# SigFoxBatteryMonitor.net
KiCad netlist of a schematic drawn in EAGLE
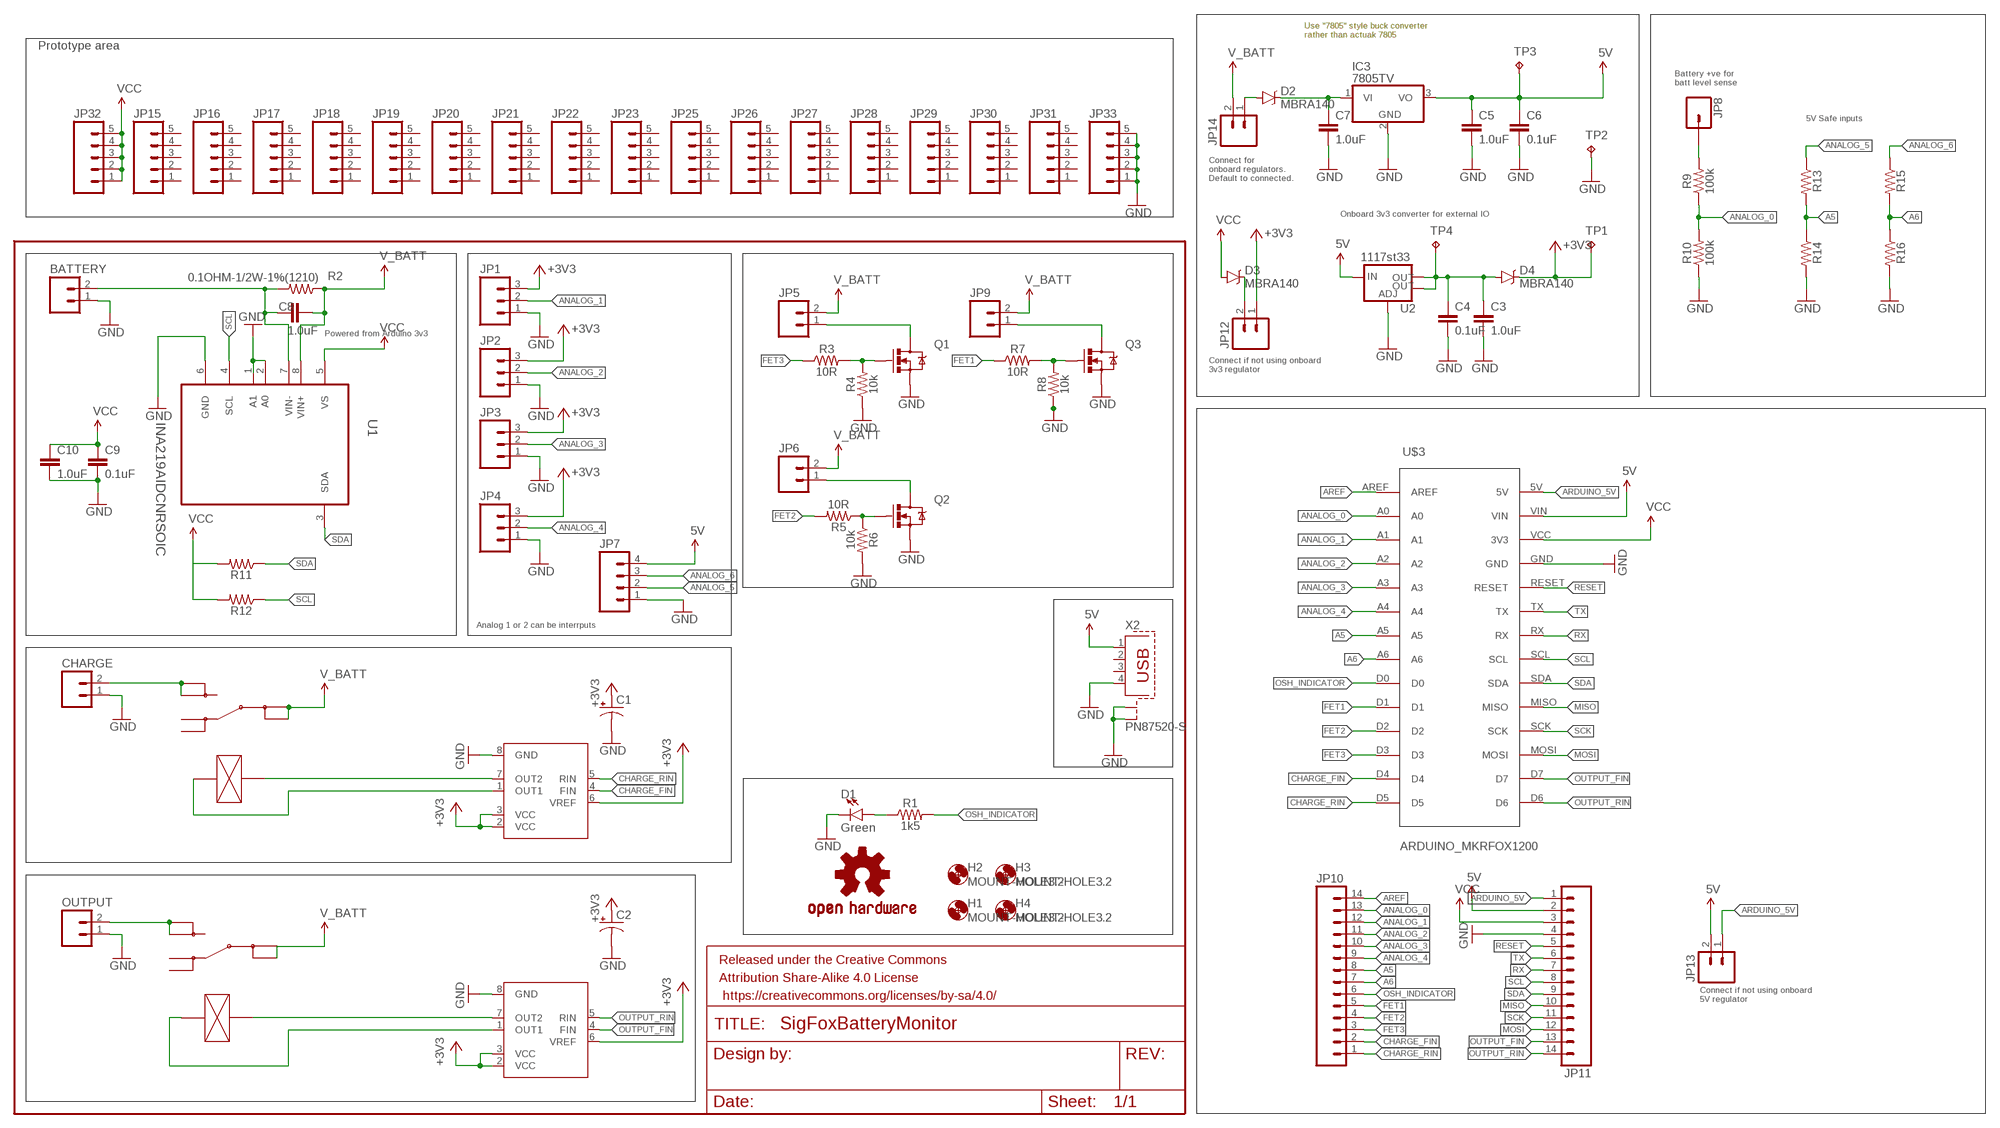
[diagram p0: schematic, sheet 1]

(export (version "E")
  (design (tool "Eeschema 10.0.6"))
  (components
    (comp (ref "BATTERY")
      (value "M025MM")
      (footprint "eagle-import:SCREWTERMINAL-5MM-2")
      (libsource (lib "eagle-import") (part "M025MM"))
    )
    (comp (ref "C1")
      (value "CAP_POL1206")
      (footprint "eagle-import:EIA3216")
      (libsource (lib "eagle-import") (part "CAP_POL1206"))
    )
    (comp (ref "C2")
      (value "CAP_POL1206")
      (footprint "eagle-import:EIA3216")
      (libsource (lib "eagle-import") (part "CAP_POL1206"))
    )
    (comp (ref "C3")
      (value "1.0uF")
      (footprint "eagle-import:0805")
      (libsource (lib "eagle-import") (part "1.0UF-0805-25V-10%"))
    )
    (comp (ref "C4")
      (value "0.1uF")
      (footprint "eagle-import:0805")
      (libsource (lib "eagle-import") (part "1.0UF-0805-25V-10%"))
    )
    (comp (ref "C5")
      (value "1.0uF")
      (footprint "eagle-import:0805")
      (libsource (lib "eagle-import") (part "1.0UF-0805-25V-10%"))
    )
    (comp (ref "C6")
      (value "0.1uF")
      (footprint "eagle-import:0805")
      (libsource (lib "eagle-import") (part "1.0UF-0805-25V-10%"))
    )
    (comp (ref "C7")
      (value "1.0uF")
      (footprint "eagle-import:0805")
      (libsource (lib "eagle-import") (part "1.0UF-0805-25V-10%"))
    )
    (comp (ref "C8")
      (value "1.0uF")
      (footprint "eagle-import:0805")
      (libsource (lib "eagle-import") (part "1.0UF-0805-25V-10%"))
    )
    (comp (ref "C9")
      (value "0.1uF")
      (footprint "eagle-import:0805")
      (libsource (lib "eagle-import") (part "1.0UF-0805-25V-10%"))
    )
    (comp (ref "C10")
      (value "1.0uF")
      (footprint "eagle-import:0805")
      (libsource (lib "eagle-import") (part "1.0UF-0805-25V-10%"))
    )
    (comp (ref "CHARGE")
      (value "M025MM")
      (footprint "eagle-import:SCREWTERMINAL-5MM-2")
      (libsource (lib "eagle-import") (part "M025MM"))
    )
    (comp (ref "D1")
      (value "Green")
      (footprint "eagle-import:LED-1206-BOTTOM")
      (libsource (lib "eagle-import") (part "LED-GREEN1206-BOTTOM"))
    )
    (comp (ref "D2")
      (value "MBRA140")
      (footprint "eagle-import:SMA-DIODE")
      (libsource (lib "eagle-import") (part "DIODE-SCHOTTKY-MBRA140"))
    )
    (comp (ref "D3")
      (value "MBRA140")
      (footprint "eagle-import:SMA-DIODE")
      (libsource (lib "eagle-import") (part "DIODE-SCHOTTKY-MBRA140"))
    )
    (comp (ref "D4")
      (value "MBRA140")
      (footprint "eagle-import:SMA-DIODE")
      (libsource (lib "eagle-import") (part "DIODE-SCHOTTKY-MBRA140"))
    )
    (comp (ref "FRAME1")
      (value "FRAME-LETTER")
      (footprint "eagle-import:CREATIVE_COMMONS")
      (libsource (lib "eagle-import") (part "FRAME-LETTER"))
    )
    (comp (ref "H1")
      (value "MOUNT-HOLE3.2")
      (footprint "eagle-import:3,2")
      (libsource (lib "eagle-import") (part "MOUNT-HOLE3.2"))
    )
    (comp (ref "H2")
      (value "MOUNT-HOLE3.2")
      (footprint "eagle-import:3,2")
      (libsource (lib "eagle-import") (part "MOUNT-HOLE3.2"))
    )
    (comp (ref "H3")
      (value "MOUNT-HOLE3.2")
      (footprint "eagle-import:3,2")
      (libsource (lib "eagle-import") (part "MOUNT-HOLE3.2"))
    )
    (comp (ref "H4")
      (value "MOUNT-HOLE3.2")
      (footprint "eagle-import:3,2")
      (libsource (lib "eagle-import") (part "MOUNT-HOLE3.2"))
    )
    (comp (ref "IC1")
      (value "BD6211F")
      (footprint "eagle-import:SOP8")
      (libsource (lib "eagle-import") (part "BD6211F"))
    )
    (comp (ref "IC2")
      (value "BD6211F")
      (footprint "eagle-import:SOP8")
      (libsource (lib "eagle-import") (part "BD6211F"))
    )
    (comp (ref "IC3")
      (value "7805TV")
      (footprint "eagle-import:TO220V")
      (libsource (lib "eagle-import") (part "78TV05"))
    )
    (comp (ref "JP1")
      (value "M03POLAR")
      (footprint "eagle-import:MOLEX-1X3")
      (libsource (lib "eagle-import") (part "M03POLAR"))
    )
    (comp (ref "JP2")
      (value "M03POLAR")
      (footprint "eagle-import:MOLEX-1X3")
      (libsource (lib "eagle-import") (part "M03POLAR"))
    )
    (comp (ref "JP3")
      (value "M03POLAR")
      (footprint "eagle-import:MOLEX-1X3")
      (libsource (lib "eagle-import") (part "M03POLAR"))
    )
    (comp (ref "JP4")
      (value "M03POLAR")
      (footprint "eagle-import:MOLEX-1X3")
      (libsource (lib "eagle-import") (part "M03POLAR"))
    )
    (comp (ref "JP5")
      (value "M02POLAR")
      (footprint "eagle-import:MOLEX-1X2")
      (libsource (lib "eagle-import") (part "M02POLAR"))
    )
    (comp (ref "JP6")
      (value "M02POLAR")
      (footprint "eagle-import:MOLEX-1X2")
      (libsource (lib "eagle-import") (part "M02POLAR"))
    )
    (comp (ref "JP7")
      (value "M04POLAR")
      (footprint "eagle-import:MOLEX-1X4")
      (libsource (lib "eagle-import") (part "M04POLAR"))
    )
    (comp (ref "JP8")
      (value "M01PTH")
      (footprint "eagle-import:1X01")
      (libsource (lib "eagle-import") (part "M01PTH"))
    )
    (comp (ref "JP9")
      (value "M02POLAR")
      (footprint "eagle-import:MOLEX-1X2")
      (libsource (lib "eagle-import") (part "M02POLAR"))
    )
    (comp (ref "JP10")
      (value "M14")
      (footprint "eagle-import:1X14")
      (libsource (lib "eagle-import") (part "M14"))
    )
    (comp (ref "JP11")
      (value "M14")
      (footprint "eagle-import:1X14")
      (libsource (lib "eagle-import") (part "M14"))
    )
    (comp (ref "JP12")
      (value "M02PTH")
      (footprint "eagle-import:1X02")
      (libsource (lib "eagle-import") (part "M02PTH"))
    )
    (comp (ref "JP13")
      (value "M02PTH")
      (footprint "eagle-import:1X02")
      (libsource (lib "eagle-import") (part "M02PTH"))
    )
    (comp (ref "JP14")
      (value "M02PTH")
      (footprint "eagle-import:1X02")
      (libsource (lib "eagle-import") (part "M02PTH"))
    )
    (comp (ref "JP15")
      (value "M05NO_SILK")
      (footprint "eagle-import:1X05_NO_SILK")
      (libsource (lib "eagle-import") (part "M05NO_SILK"))
    )
    (comp (ref "JP16")
      (value "M05NO_SILK")
      (footprint "eagle-import:1X05_NO_SILK")
      (libsource (lib "eagle-import") (part "M05NO_SILK"))
    )
    (comp (ref "JP17")
      (value "M05NO_SILK")
      (footprint "eagle-import:1X05_NO_SILK")
      (libsource (lib "eagle-import") (part "M05NO_SILK"))
    )
    (comp (ref "JP18")
      (value "M05NO_SILK")
      (footprint "eagle-import:1X05_NO_SILK")
      (libsource (lib "eagle-import") (part "M05NO_SILK"))
    )
    (comp (ref "JP19")
      (value "M05NO_SILK")
      (footprint "eagle-import:1X05_NO_SILK")
      (libsource (lib "eagle-import") (part "M05NO_SILK"))
    )
    (comp (ref "JP20")
      (value "M05NO_SILK")
      (footprint "eagle-import:1X05_NO_SILK")
      (libsource (lib "eagle-import") (part "M05NO_SILK"))
    )
    (comp (ref "JP21")
      (value "M05NO_SILK")
      (footprint "eagle-import:1X05_NO_SILK")
      (libsource (lib "eagle-import") (part "M05NO_SILK"))
    )
    (comp (ref "JP22")
      (value "M05NO_SILK")
      (footprint "eagle-import:1X05_NO_SILK")
      (libsource (lib "eagle-import") (part "M05NO_SILK"))
    )
    (comp (ref "JP23")
      (value "M05NO_SILK")
      (footprint "eagle-import:1X05_NO_SILK")
      (libsource (lib "eagle-import") (part "M05NO_SILK"))
    )
    (comp (ref "JP25")
      (value "M05NO_SILK")
      (footprint "eagle-import:1X05_NO_SILK")
      (libsource (lib "eagle-import") (part "M05NO_SILK"))
    )
    (comp (ref "JP26")
      (value "M05NO_SILK")
      (footprint "eagle-import:1X05_NO_SILK")
      (libsource (lib "eagle-import") (part "M05NO_SILK"))
    )
    (comp (ref "JP27")
      (value "M05NO_SILK")
      (footprint "eagle-import:1X05_NO_SILK")
      (libsource (lib "eagle-import") (part "M05NO_SILK"))
    )
    (comp (ref "JP28")
      (value "M05NO_SILK")
      (footprint "eagle-import:1X05_NO_SILK")
      (libsource (lib "eagle-import") (part "M05NO_SILK"))
    )
    (comp (ref "JP29")
      (value "M05NO_SILK")
      (footprint "eagle-import:1X05_NO_SILK")
      (libsource (lib "eagle-import") (part "M05NO_SILK"))
    )
    (comp (ref "JP30")
      (value "M05NO_SILK")
      (footprint "eagle-import:1X05_NO_SILK")
      (libsource (lib "eagle-import") (part "M05NO_SILK"))
    )
    (comp (ref "JP31")
      (value "M05NO_SILK")
      (footprint "eagle-import:1X05_NO_SILK")
      (libsource (lib "eagle-import") (part "M05NO_SILK"))
    )
    (comp (ref "JP32")
      (value "M05PTH")
      (footprint "eagle-import:1X05")
      (libsource (lib "eagle-import") (part "M05PTH"))
    )
    (comp (ref "JP33")
      (value "M05PTH")
      (footprint "eagle-import:1X05")
      (libsource (lib "eagle-import") (part "M05PTH"))
    )
    (comp (ref "LOGO1")
      (value "OSHW-LOGOM")
      (footprint "eagle-import:OSHW-LOGO-M")
      (libsource (lib "eagle-import") (part "OSHW-LOGOM"))
    )
    (comp (ref "OUTPUT")
      (value "M025MM")
      (footprint "eagle-import:SCREWTERMINAL-5MM-2")
      (libsource (lib "eagle-import") (part "M025MM"))
    )
    (comp (ref "Q1")
      (value "IRF7413Z")
      (footprint "eagle-import:SO08")
      (libsource (lib "eagle-import") (part "MOSFET-NCHANNELFDS6630A"))
    )
    (comp (ref "Q2")
      (value "IRF7413Z")
      (footprint "eagle-import:SO08")
      (libsource (lib "eagle-import") (part "MOSFET-NCHANNELFDS6630A"))
    )
    (comp (ref "Q3")
      (value "IRF7413Z")
      (footprint "eagle-import:SO08")
      (libsource (lib "eagle-import") (part "MOSFET-NCHANNELFDS6630A"))
    )
    (comp (ref "R1")
      (value "1k5")
      (footprint "eagle-import:1206")
      (libsource (lib "eagle-import") (part "RESISTOR1206"))
    )
    (comp (ref "R2")
      (value "0.1OHM-1/2W-1%(1210)")
      (footprint "eagle-import:1210")
      (libsource (lib "eagle-import") (part "0.1OHM-1/2W-1%(1210)"))
    )
    (comp (ref "R3")
      (value "10R")
      (footprint "eagle-import:0805")
      (libsource (lib "eagle-import") (part "RESISTOR0805"))
    )
    (comp (ref "R4")
      (value "10k")
      (footprint "eagle-import:0805")
      (libsource (lib "eagle-import") (part "RESISTOR0805"))
    )
    (comp (ref "R5")
      (value "10R")
      (footprint "eagle-import:0805")
      (libsource (lib "eagle-import") (part "RESISTOR0805"))
    )
    (comp (ref "R6")
      (value "10k")
      (footprint "eagle-import:0805")
      (libsource (lib "eagle-import") (part "RESISTOR0805"))
    )
    (comp (ref "R7")
      (value "10R")
      (footprint "eagle-import:0805")
      (libsource (lib "eagle-import") (part "RESISTOR0805"))
    )
    (comp (ref "R8")
      (value "10k")
      (footprint "eagle-import:0805")
      (libsource (lib "eagle-import") (part "RESISTOR0805"))
    )
    (comp (ref "R9")
      (value "100k")
      (footprint "eagle-import:0805")
      (libsource (lib "eagle-import") (part "RESISTOR0805"))
    )
    (comp (ref "R10")
      (value "100k")
      (footprint "eagle-import:0805")
      (libsource (lib "eagle-import") (part "RESISTOR0805"))
    )
    (comp (ref "R11")
      (value "RESISTOR0805")
      (footprint "eagle-import:0805")
      (libsource (lib "eagle-import") (part "RESISTOR0805"))
    )
    (comp (ref "R12")
      (value "RESISTOR0805")
      (footprint "eagle-import:0805")
      (libsource (lib "eagle-import") (part "RESISTOR0805"))
    )
    (comp (ref "R13")
      (value "RESISTOR0805")
      (footprint "eagle-import:0805")
      (libsource (lib "eagle-import") (part "RESISTOR0805"))
    )
    (comp (ref "R14")
      (value "RESISTOR0805")
      (footprint "eagle-import:0805")
      (libsource (lib "eagle-import") (part "RESISTOR0805"))
    )
    (comp (ref "R15")
      (value "RESISTOR0805")
      (footprint "eagle-import:0805")
      (libsource (lib "eagle-import") (part "RESISTOR0805"))
    )
    (comp (ref "R16")
      (value "RESISTOR0805")
      (footprint "eagle-import:0805")
      (libsource (lib "eagle-import") (part "RESISTOR0805"))
    )
    (comp (ref "TP1")
      (value "3v3")
      (footprint "eagle-import:TP15R")
      (libsource (lib "eagle-import") (part "TPTP15R"))
    )
    (comp (ref "TP2")
      (value "GND")
      (footprint "eagle-import:TP15R")
      (libsource (lib "eagle-import") (part "TPTP15R"))
    )
    (comp (ref "TP3")
      (value "5v")
      (footprint "eagle-import:TP15R")
      (libsource (lib "eagle-import") (part "TPTP15R"))
    )
    (comp (ref "TP4")
      (value "5v")
      (footprint "eagle-import:TP15R")
      (libsource (lib "eagle-import") (part "TPTP15R"))
    )
    (comp (ref "U$1")
      (value "RELAY_G5RL-1E")
      (footprint "eagle-import:G5RL-1E")
      (libsource (lib "eagle-import") (part "RELAY_G5RL-1E"))
    )
    (comp (ref "U$2")
      (value "RELAY_G5RL-1E")
      (footprint "eagle-import:G5RL-1E")
      (libsource (lib "eagle-import") (part "RELAY_G5RL-1E"))
    )
    (comp (ref "U$3")
      (value "ARDUINO_MKRFOX1200")
      (footprint "eagle-import:ARDUINO_MKRFOX1200")
      (libsource (lib "eagle-import") (part "ARDUINO_MKRFOX1200"))
    )
    (comp (ref "U1")
      (value "INA219AIDCNRSOIC")
      (footprint "eagle-import:SO08")
      (libsource (lib "eagle-import") (part "INA219AIDCNRSOIC"))
    )
    (comp (ref "U2")
      (value "1117st33")
      (footprint "eagle-import:SOT223")
      (libsource (lib "eagle-import") (part "V_REG_LM1117SOT223"))
    )
    (comp (ref "X2")
      (value "PN87520-S")
      (footprint "eagle-import:PN87520-S")
      (libsource (lib "eagle-import") (part "PN87520-S"))
    )
  )
  (nets
    (net (code "1") (name "+3V3") (class "Default")
      (node (ref "C1") (pin "A") (pinfunction "+_A") (pintype "passive"))
      (node (ref "C2") (pin "A") (pinfunction "+_A") (pintype "passive"))
      (node (ref "D4") (pin "C") (pinfunction "C_C") (pintype "passive"))
      (node (ref "IC1") (pin "2") (pinfunction "VCC_2") (pintype "power_in"))
      (node (ref "IC1") (pin "3") (pinfunction "VCC_3") (pintype "power_in"))
      (node (ref "IC1") (pin "6") (pinfunction "VREF_6") (pintype "passive"))
      (node (ref "IC2") (pin "2") (pinfunction "VCC_2") (pintype "power_in"))
      (node (ref "IC2") (pin "3") (pinfunction "VCC_3") (pintype "power_in"))
      (node (ref "IC2") (pin "6") (pinfunction "VREF_6") (pintype "passive"))
      (node (ref "JP1") (pin "3") (pinfunction "3_3") (pintype "passive"))
      (node (ref "JP12") (pin "1") (pinfunction "1_1") (pintype "passive"))
      (node (ref "JP2") (pin "3") (pinfunction "3_3") (pintype "passive"))
      (node (ref "JP3") (pin "3") (pinfunction "3_3") (pintype "passive"))
      (node (ref "JP4") (pin "3") (pinfunction "3_3") (pintype "passive"))
      (node (ref "TP1") (pin "TP") (pinfunction "TP_TP") (pintype "input"))
    )
    (net (code "2") (name "5V") (class "Default")
      (node (ref "C5") (pin "1") (pinfunction "1_1") (pintype "passive"))
      (node (ref "C6") (pin "1") (pinfunction "1_1") (pintype "passive"))
      (node (ref "IC3") (pin "3") (pinfunction "VO_3") (pintype "passive"))
      (node (ref "JP11") (pin "2") (pinfunction "2_2") (pintype "passive"))
      (node (ref "JP13") (pin "2") (pinfunction "2_2") (pintype "passive"))
      (node (ref "JP7") (pin "4") (pinfunction "4_4") (pintype "passive"))
      (node (ref "TP3") (pin "TP") (pinfunction "TP_TP") (pintype "input"))
      (node (ref "U$3") (pin "VIN") (pinfunction "VIN_VIN") (pintype "input"))
      (node (ref "U2") (pin "3") (pinfunction "IN_3") (pintype "input"))
      (node (ref "X2") (pin "1") (pinfunction "1_1") (pintype "passive"))
    )
    (net (code "3") (name "A5") (class "Default")
      (node (ref "JP10") (pin "8") (pinfunction "8_8") (pintype "passive"))
      (node (ref "R13") (pin "2") (pinfunction "2_2") (pintype "passive"))
      (node (ref "R14") (pin "1") (pinfunction "1_1") (pintype "passive"))
      (node (ref "U$3") (pin "A5") (pinfunction "A5_A5") (pintype "bidirectional"))
    )
    (net (code "4") (name "A6") (class "Default")
      (node (ref "JP10") (pin "7") (pinfunction "7_7") (pintype "passive"))
      (node (ref "R15") (pin "2") (pinfunction "2_2") (pintype "passive"))
      (node (ref "R16") (pin "1") (pinfunction "1_1") (pintype "passive"))
      (node (ref "U$3") (pin "A6") (pinfunction "A6_A6") (pintype "bidirectional"))
    )
    (net (code "5") (name "ANALOG_0") (class "Default")
      (node (ref "JP10") (pin "13") (pinfunction "13_13") (pintype "passive"))
      (node (ref "R10") (pin "2") (pinfunction "2_2") (pintype "passive"))
      (node (ref "R9") (pin "1") (pinfunction "1_1") (pintype "passive"))
      (node (ref "U$3") (pin "A0") (pinfunction "A0_A0") (pintype "bidirectional"))
    )
    (net (code "6") (name "ANALOG_1") (class "Default")
      (node (ref "JP1") (pin "2") (pinfunction "2_2") (pintype "passive"))
      (node (ref "JP10") (pin "12") (pinfunction "12_12") (pintype "passive"))
      (node (ref "U$3") (pin "A1") (pinfunction "A1_A1") (pintype "bidirectional"))
    )
    (net (code "7") (name "ANALOG_2") (class "Default")
      (node (ref "JP10") (pin "11") (pinfunction "11_11") (pintype "passive"))
      (node (ref "JP2") (pin "2") (pinfunction "2_2") (pintype "passive"))
      (node (ref "U$3") (pin "A2") (pinfunction "A2_A2") (pintype "bidirectional"))
    )
    (net (code "8") (name "ANALOG_3") (class "Default")
      (node (ref "JP10") (pin "10") (pinfunction "10_10") (pintype "passive"))
      (node (ref "JP3") (pin "2") (pinfunction "2_2") (pintype "passive"))
      (node (ref "U$3") (pin "A3") (pinfunction "A3_A3") (pintype "bidirectional"))
    )
    (net (code "9") (name "ANALOG_4") (class "Default")
      (node (ref "JP10") (pin "9") (pinfunction "9_9") (pintype "passive"))
      (node (ref "JP4") (pin "2") (pinfunction "2_2") (pintype "passive"))
      (node (ref "U$3") (pin "A4") (pinfunction "A4_A4") (pintype "bidirectional"))
    )
    (net (code "10") (name "ANALOG_5") (class "Default")
      (node (ref "JP7") (pin "2") (pinfunction "2_2") (pintype "passive"))
      (node (ref "R13") (pin "1") (pinfunction "1_1") (pintype "passive"))
    )
    (net (code "11") (name "ANALOG_6") (class "Default")
      (node (ref "JP7") (pin "3") (pinfunction "3_3") (pintype "passive"))
      (node (ref "R15") (pin "1") (pinfunction "1_1") (pintype "passive"))
    )
    (net (code "12") (name "ARDUINO_5V") (class "Default")
      (node (ref "JP11") (pin "1") (pinfunction "1_1") (pintype "passive"))
      (node (ref "JP13") (pin "1") (pinfunction "1_1") (pintype "passive"))
      (node (ref "U$3") (pin "5V") (pinfunction "5V_5V") (pintype "output"))
    )
    (net (code "13") (name "AREF") (class "Default")
      (node (ref "JP10") (pin "14") (pinfunction "14_14") (pintype "passive"))
      (node (ref "U$3") (pin "AREF") (pinfunction "AREF_AREF") (pintype "bidirectional"))
    )
    (net (code "14") (name "CHARGE_FIN") (class "Default")
      (node (ref "IC1") (pin "4") (pinfunction "FIN_4") (pintype "input"))
      (node (ref "JP10") (pin "2") (pinfunction "2_2") (pintype "passive"))
      (node (ref "U$3") (pin "D4") (pinfunction "D4_D4") (pintype "bidirectional"))
    )
    (net (code "15") (name "CHARGE_RIN") (class "Default")
      (node (ref "IC1") (pin "5") (pinfunction "RIN_5") (pintype "input"))
      (node (ref "JP10") (pin "1") (pinfunction "1_1") (pintype "passive"))
      (node (ref "U$3") (pin "D5") (pinfunction "D5_D5") (pintype "bidirectional"))
    )
    (net (code "16") (name "FET1") (class "Default")
      (node (ref "JP10") (pin "5") (pinfunction "5_5") (pintype "passive"))
      (node (ref "R7") (pin "1") (pinfunction "1_1") (pintype "passive"))
      (node (ref "U$3") (pin "D1") (pinfunction "D1_D1") (pintype "bidirectional"))
    )
    (net (code "17") (name "FET2") (class "Default")
      (node (ref "JP10") (pin "4") (pinfunction "4_4") (pintype "passive"))
      (node (ref "R5") (pin "2") (pinfunction "2_2") (pintype "passive"))
      (node (ref "U$3") (pin "D2") (pinfunction "D2_D2") (pintype "bidirectional"))
    )
    (net (code "18") (name "FET3") (class "Default")
      (node (ref "JP10") (pin "3") (pinfunction "3_3") (pintype "passive"))
      (node (ref "R3") (pin "1") (pinfunction "1_1") (pintype "passive"))
      (node (ref "U$3") (pin "D3") (pinfunction "D3_D3") (pintype "bidirectional"))
    )
    (net (code "19") (name "GND") (class "Default")
      (node (ref "BATTERY") (pin "1") (pinfunction "1_1") (pintype "passive"))
      (node (ref "C1") (pin "C") (pinfunction "-_C") (pintype "passive"))
      (node (ref "C10") (pin "2") (pinfunction "2_2") (pintype "passive"))
      (node (ref "C2") (pin "C") (pinfunction "-_C") (pintype "passive"))
      (node (ref "C3") (pin "2") (pinfunction "2_2") (pintype "passive"))
      (node (ref "C4") (pin "2") (pinfunction "2_2") (pintype "passive"))
      (node (ref "C5") (pin "2") (pinfunction "2_2") (pintype "passive"))
      (node (ref "C6") (pin "2") (pinfunction "2_2") (pintype "passive"))
      (node (ref "C7") (pin "2") (pinfunction "2_2") (pintype "passive"))
      (node (ref "C9") (pin "2") (pinfunction "2_2") (pintype "passive"))
      (node (ref "CHARGE") (pin "1") (pinfunction "1_1") (pintype "passive"))
      (node (ref "D1") (pin "C") (pinfunction "C_C") (pintype "passive"))
      (node (ref "IC1") (pin "8") (pinfunction "GND_8") (pintype "power_in"))
      (node (ref "IC2") (pin "8") (pinfunction "GND_8") (pintype "power_in"))
      (node (ref "IC3") (pin "2") (pinfunction "GND_2") (pintype "passive"))
      (node (ref "JP1") (pin "1") (pinfunction "1_1") (pintype "passive"))
      (node (ref "JP11") (pin "4") (pinfunction "4_4") (pintype "passive"))
      (node (ref "JP2") (pin "1") (pinfunction "1_1") (pintype "passive"))
      (node (ref "JP3") (pin "1") (pinfunction "1_1") (pintype "passive"))
      (node (ref "JP33") (pin "1") (pinfunction "1_1") (pintype "passive"))
      (node (ref "JP33") (pin "2") (pinfunction "2_2") (pintype "passive"))
      (node (ref "JP33") (pin "3") (pinfunction "3_3") (pintype "passive"))
      (node (ref "JP33") (pin "4") (pinfunction "4_4") (pintype "passive"))
      (node (ref "JP33") (pin "5") (pinfunction "5_5") (pintype "passive"))
      (node (ref "JP4") (pin "1") (pinfunction "1_1") (pintype "passive"))
      (node (ref "JP7") (pin "1") (pinfunction "1_1") (pintype "passive"))
      (node (ref "OUTPUT") (pin "1") (pinfunction "1_1") (pintype "passive"))
      (node (ref "Q1") (pin "1") (pinfunction "S_1") (pintype "passive"))
      (node (ref "Q1") (pin "2") (pinfunction "S_2") (pintype "passive"))
      (node (ref "Q1") (pin "3") (pinfunction "S_3") (pintype "passive"))
      (node (ref "Q2") (pin "1") (pinfunction "S_1") (pintype "passive"))
      (node (ref "Q2") (pin "2") (pinfunction "S_2") (pintype "passive"))
      (node (ref "Q2") (pin "3") (pinfunction "S_3") (pintype "passive"))
      (node (ref "Q3") (pin "1") (pinfunction "S_1") (pintype "passive"))
      (node (ref "Q3") (pin "2") (pinfunction "S_2") (pintype "passive"))
      (node (ref "Q3") (pin "3") (pinfunction "S_3") (pintype "passive"))
      (node (ref "R10") (pin "1") (pinfunction "1_1") (pintype "passive"))
      (node (ref "R14") (pin "2") (pinfunction "2_2") (pintype "passive"))
      (node (ref "R16") (pin "2") (pinfunction "2_2") (pintype "passive"))
      (node (ref "R4") (pin "1") (pinfunction "1_1") (pintype "passive"))
      (node (ref "R6") (pin "2") (pinfunction "2_2") (pintype "passive"))
      (node (ref "R8") (pin "1") (pinfunction "1_1") (pintype "passive"))
      (node (ref "TP2") (pin "TP") (pinfunction "TP_TP") (pintype "input"))
      (node (ref "U$3") (pin "GND") (pinfunction "GND_GND") (pintype "power_in"))
      (node (ref "U1") (pin "1") (pinfunction "A1_1") (pintype "input"))
      (node (ref "U1") (pin "2") (pinfunction "A0_2") (pintype "input"))
      (node (ref "U1") (pin "6") (pinfunction "GND_6") (pintype "passive"))
      (node (ref "U2") (pin "1") (pinfunction "ADJ_1") (pintype "input"))
      (node (ref "X2") (pin "4") (pinfunction "4_4") (pintype "passive"))
      (node (ref "X2") (pin "S1") (pinfunction "S1_S1") (pintype "passive"))
      (node (ref "X2") (pin "S2") (pinfunction "S2_S2") (pintype "passive"))
    )
    (net (code "20") (name "MISO") (class "Default")
      (node (ref "JP11") (pin "10") (pinfunction "10_10") (pintype "passive"))
      (node (ref "U$3") (pin "MISO") (pinfunction "MISO_MISO") (pintype "bidirectional"))
    )
    (net (code "21") (name "MOSI") (class "Default")
      (node (ref "JP11") (pin "12") (pinfunction "12_12") (pintype "passive"))
      (node (ref "U$3") (pin "MOSI") (pinfunction "MOSI_MOSI") (pintype "bidirectional"))
    )
    (net (code "22") (name "Net-(C3-Pad1)") (class "Default")
      (node (ref "C3") (pin "1") (pinfunction "1_1") (pintype "passive"))
      (node (ref "C4") (pin "1") (pinfunction "1_1") (pintype "passive"))
      (node (ref "D4") (pin "A") (pinfunction "A_A") (pintype "passive"))
      (node (ref "TP4") (pin "TP") (pinfunction "TP_TP") (pintype "input"))
      (node (ref "U2") (pin "2") (pinfunction "OUT_2") (pintype "output"))
      (node (ref "U2") (pin "4") (pinfunction "OUT_4") (pintype "output"))
    )
    (net (code "23") (name "Net-(CHARGE-Pad2)") (class "Default")
      (node (ref "CHARGE") (pin "2") (pinfunction "2_2") (pintype "passive"))
      (node (ref "U$2") (pin "NO@1") (pinfunction "NO_NO@1") (pintype "bidirectional"))
      (node (ref "U$2") (pin "NO@2") (pinfunction "NO_NO@2") (pintype "bidirectional"))
    )
    (net (code "24") (name "Net-(D1-PadA)") (class "Default")
      (node (ref "D1") (pin "A") (pinfunction "A_A") (pintype "passive"))
      (node (ref "R1") (pin "1") (pinfunction "1_1") (pintype "passive"))
    )
    (net (code "25") (name "Net-(D2-PadA)") (class "Default")
      (node (ref "D2") (pin "A") (pinfunction "A_A") (pintype "passive"))
      (node (ref "JP14") (pin "1") (pinfunction "1_1") (pintype "passive"))
    )
    (net (code "26") (name "Net-(D3-PadC)") (class "Default")
      (node (ref "D3") (pin "C") (pinfunction "C_C") (pintype "passive"))
      (node (ref "JP12") (pin "2") (pinfunction "2_2") (pintype "passive"))
    )
    (net (code "27") (name "Net-(IC1-OUT1)") (class "Default")
      (node (ref "IC1") (pin "1") (pinfunction "OUT1_1") (pintype "output"))
      (node (ref "U$2") (pin "COIL+") (pinfunction "COIL+_COIL+") (pintype "bidirectional"))
    )
    (net (code "28") (name "Net-(IC1-OUT2)") (class "Default")
      (node (ref "IC1") (pin "7") (pinfunction "OUT2_7") (pintype "output"))
      (node (ref "U$2") (pin "COIL-") (pinfunction "COIL-_COIL-") (pintype "bidirectional"))
    )
    (net (code "29") (name "Net-(IC2-OUT1)") (class "Default")
      (node (ref "IC2") (pin "1") (pinfunction "OUT1_1") (pintype "output"))
      (node (ref "U$1") (pin "COIL+") (pinfunction "COIL+_COIL+") (pintype "bidirectional"))
    )
    (net (code "30") (name "Net-(IC2-OUT2)") (class "Default")
      (node (ref "IC2") (pin "7") (pinfunction "OUT2_7") (pintype "output"))
      (node (ref "U$1") (pin "COIL-") (pinfunction "COIL-_COIL-") (pintype "bidirectional"))
    )
    (net (code "31") (name "Net-(IC3-VI)") (class "Default")
      (node (ref "C7") (pin "1") (pinfunction "1_1") (pintype "passive"))
      (node (ref "D2") (pin "C") (pinfunction "C_C") (pintype "passive"))
      (node (ref "IC3") (pin "1") (pinfunction "VI_1") (pintype "input"))
    )
    (net (code "32") (name "Net-(JP5-Pad1)") (class "Default")
      (node (ref "JP5") (pin "1") (pinfunction "1_1") (pintype "passive"))
      (node (ref "Q1") (pin "5") (pinfunction "D_5") (pintype "passive"))
      (node (ref "Q1") (pin "6") (pinfunction "D_6") (pintype "passive"))
      (node (ref "Q1") (pin "7") (pinfunction "D_7") (pintype "passive"))
      (node (ref "Q1") (pin "8") (pinfunction "D_8") (pintype "passive"))
    )
    (net (code "33") (name "Net-(JP6-Pad1)") (class "Default")
      (node (ref "JP6") (pin "1") (pinfunction "1_1") (pintype "passive"))
      (node (ref "Q2") (pin "5") (pinfunction "D_5") (pintype "passive"))
      (node (ref "Q2") (pin "6") (pinfunction "D_6") (pintype "passive"))
      (node (ref "Q2") (pin "7") (pinfunction "D_7") (pintype "passive"))
      (node (ref "Q2") (pin "8") (pinfunction "D_8") (pintype "passive"))
    )
    (net (code "34") (name "Net-(JP8-Pad1)") (class "Default")
      (node (ref "JP8") (pin "1") (pinfunction "1_1") (pintype "passive"))
      (node (ref "R9") (pin "2") (pinfunction "2_2") (pintype "passive"))
    )
    (net (code "35") (name "Net-(JP9-Pad1)") (class "Default")
      (node (ref "JP9") (pin "1") (pinfunction "1_1") (pintype "passive"))
      (node (ref "Q3") (pin "5") (pinfunction "D_5") (pintype "passive"))
      (node (ref "Q3") (pin "6") (pinfunction "D_6") (pintype "passive"))
      (node (ref "Q3") (pin "7") (pinfunction "D_7") (pintype "passive"))
      (node (ref "Q3") (pin "8") (pinfunction "D_8") (pintype "passive"))
    )
    (net (code "36") (name "Net-(OUTPUT-Pad2)") (class "Default")
      (node (ref "OUTPUT") (pin "2") (pinfunction "2_2") (pintype "passive"))
      (node (ref "U$1") (pin "NO@1") (pinfunction "NO_NO@1") (pintype "bidirectional"))
      (node (ref "U$1") (pin "NO@2") (pinfunction "NO_NO@2") (pintype "bidirectional"))
    )
    (net (code "37") (name "Net-(Q1-G)") (class "Default")
      (node (ref "Q1") (pin "4") (pinfunction "G_4") (pintype "passive"))
      (node (ref "R3") (pin "2") (pinfunction "2_2") (pintype "passive"))
      (node (ref "R4") (pin "2") (pinfunction "2_2") (pintype "passive"))
    )
    (net (code "38") (name "Net-(Q2-G)") (class "Default")
      (node (ref "Q2") (pin "4") (pinfunction "G_4") (pintype "passive"))
      (node (ref "R5") (pin "1") (pinfunction "1_1") (pintype "passive"))
      (node (ref "R6") (pin "1") (pinfunction "1_1") (pintype "passive"))
    )
    (net (code "39") (name "Net-(Q3-G)") (class "Default")
      (node (ref "Q3") (pin "4") (pinfunction "G_4") (pintype "passive"))
      (node (ref "R7") (pin "2") (pinfunction "2_2") (pintype "passive"))
      (node (ref "R8") (pin "2") (pinfunction "2_2") (pintype "passive"))
    )
    (net (code "40") (name "Net-(U1-VIN-)") (class "Default")
      (node (ref "BATTERY") (pin "2") (pinfunction "2_2") (pintype "passive"))
      (node (ref "C8") (pin "1") (pinfunction "1_1") (pintype "passive"))
      (node (ref "R2") (pin "2") (pinfunction "2_2") (pintype "passive"))
      (node (ref "U1") (pin "7") (pinfunction "VIN-_7") (pintype "input"))
    )
    (net (code "41") (name "OSH_INDICATOR") (class "Default")
      (node (ref "JP10") (pin "6") (pinfunction "6_6") (pintype "passive"))
      (node (ref "R1") (pin "2") (pinfunction "2_2") (pintype "passive"))
      (node (ref "U$3") (pin "D0") (pinfunction "D0_D0") (pintype "bidirectional"))
    )
    (net (code "42") (name "OUTPUT_FIN") (class "Default")
      (node (ref "IC2") (pin "4") (pinfunction "FIN_4") (pintype "input"))
      (node (ref "JP11") (pin "13") (pinfunction "13_13") (pintype "passive"))
      (node (ref "U$3") (pin "D7") (pinfunction "D7_D7") (pintype "bidirectional"))
    )
    (net (code "43") (name "OUTPUT_RIN") (class "Default")
      (node (ref "IC2") (pin "5") (pinfunction "RIN_5") (pintype "input"))
      (node (ref "JP11") (pin "14") (pinfunction "14_14") (pintype "passive"))
      (node (ref "U$3") (pin "D6") (pinfunction "D6_D6") (pintype "bidirectional"))
    )
    (net (code "44") (name "RESET") (class "Default")
      (node (ref "JP11") (pin "5") (pinfunction "5_5") (pintype "passive"))
      (node (ref "U$3") (pin "RESET") (pinfunction "RESET_RESET") (pintype "bidirectional"))
    )
    (net (code "45") (name "RX") (class "Default")
      (node (ref "JP11") (pin "7") (pinfunction "7_7") (pintype "passive"))
      (node (ref "U$3") (pin "RX") (pinfunction "RX_RX") (pintype "bidirectional"))
    )
    (net (code "46") (name "SCK") (class "Default")
      (node (ref "JP11") (pin "11") (pinfunction "11_11") (pintype "passive"))
      (node (ref "U$3") (pin "SCK") (pinfunction "SCK_SCK") (pintype "bidirectional"))
    )
    (net (code "47") (name "SCL") (class "Default")
      (node (ref "JP11") (pin "8") (pinfunction "8_8") (pintype "passive"))
      (node (ref "R12") (pin "1") (pinfunction "1_1") (pintype "passive"))
      (node (ref "U$3") (pin "SCL") (pinfunction "SCL_SCL") (pintype "bidirectional"))
      (node (ref "U1") (pin "4") (pinfunction "SCL_4") (pintype "input"))
    )
    (net (code "48") (name "SDA") (class "Default")
      (node (ref "JP11") (pin "9") (pinfunction "9_9") (pintype "passive"))
      (node (ref "R11") (pin "1") (pinfunction "1_1") (pintype "passive"))
      (node (ref "U$3") (pin "SDA") (pinfunction "SDA_SDA") (pintype "bidirectional"))
      (node (ref "U1") (pin "3") (pinfunction "SDA_3") (pintype "bidirectional"))
    )
    (net (code "49") (name "TX") (class "Default")
      (node (ref "JP11") (pin "6") (pinfunction "6_6") (pintype "passive"))
      (node (ref "U$3") (pin "TX") (pinfunction "TX_TX") (pintype "bidirectional"))
    )
    (net (code "50") (name "VCC") (class "Default")
      (node (ref "C10") (pin "1") (pinfunction "1_1") (pintype "passive"))
      (node (ref "C9") (pin "1") (pinfunction "1_1") (pintype "passive"))
      (node (ref "D3") (pin "A") (pinfunction "A_A") (pintype "passive"))
      (node (ref "JP11") (pin "3") (pinfunction "3_3") (pintype "passive"))
      (node (ref "JP32") (pin "1") (pinfunction "1_1") (pintype "passive"))
      (node (ref "JP32") (pin "2") (pinfunction "2_2") (pintype "passive"))
      (node (ref "JP32") (pin "3") (pinfunction "3_3") (pintype "passive"))
      (node (ref "JP32") (pin "4") (pinfunction "4_4") (pintype "passive"))
      (node (ref "JP32") (pin "5") (pinfunction "5_5") (pintype "passive"))
      (node (ref "R11") (pin "2") (pinfunction "2_2") (pintype "passive"))
      (node (ref "R12") (pin "2") (pinfunction "2_2") (pintype "passive"))
      (node (ref "U$3") (pin "VCC") (pinfunction "3V3_VCC") (pintype "output"))
      (node (ref "U1") (pin "5") (pinfunction "VS_5") (pintype "power_in"))
    )
    (net (code "51") (name "V_BATT") (class "Default")
      (node (ref "C8") (pin "2") (pinfunction "2_2") (pintype "passive"))
      (node (ref "JP14") (pin "2") (pinfunction "2_2") (pintype "passive"))
      (node (ref "JP5") (pin "2") (pinfunction "2_2") (pintype "passive"))
      (node (ref "JP6") (pin "2") (pinfunction "2_2") (pintype "passive"))
      (node (ref "JP9") (pin "2") (pinfunction "2_2") (pintype "passive"))
      (node (ref "R2") (pin "1") (pinfunction "1_1") (pintype "passive"))
      (node (ref "U$1") (pin "COM@1") (pinfunction "COM_COM@1") (pintype "bidirectional"))
      (node (ref "U$1") (pin "COM@2") (pinfunction "COM_COM@2") (pintype "bidirectional"))
      (node (ref "U$2") (pin "COM@1") (pinfunction "COM_COM@1") (pintype "bidirectional"))
      (node (ref "U$2") (pin "COM@2") (pinfunction "COM_COM@2") (pintype "bidirectional"))
      (node (ref "U1") (pin "8") (pinfunction "VIN+_8") (pintype "input"))
    )
    (net (code "52") (name "unconnected-(JP15-Pad1)") (class "Default")
      (node (ref "JP15") (pin "1") (pinfunction "1_1") (pintype "passive"))
    )
    (net (code "53") (name "unconnected-(JP15-Pad2)") (class "Default")
      (node (ref "JP15") (pin "2") (pinfunction "2_2") (pintype "passive"))
    )
    (net (code "54") (name "unconnected-(JP15-Pad3)") (class "Default")
      (node (ref "JP15") (pin "3") (pinfunction "3_3") (pintype "passive"))
    )
    (net (code "55") (name "unconnected-(JP15-Pad4)") (class "Default")
      (node (ref "JP15") (pin "4") (pinfunction "4_4") (pintype "passive"))
    )
    (net (code "56") (name "unconnected-(JP15-Pad5)") (class "Default")
      (node (ref "JP15") (pin "5") (pinfunction "5_5") (pintype "passive"))
    )
    (net (code "57") (name "unconnected-(JP16-Pad1)") (class "Default")
      (node (ref "JP16") (pin "1") (pinfunction "1_1") (pintype "passive"))
    )
    (net (code "58") (name "unconnected-(JP16-Pad2)") (class "Default")
      (node (ref "JP16") (pin "2") (pinfunction "2_2") (pintype "passive"))
    )
    (net (code "59") (name "unconnected-(JP16-Pad3)") (class "Default")
      (node (ref "JP16") (pin "3") (pinfunction "3_3") (pintype "passive"))
    )
    (net (code "60") (name "unconnected-(JP16-Pad4)") (class "Default")
      (node (ref "JP16") (pin "4") (pinfunction "4_4") (pintype "passive"))
    )
    (net (code "61") (name "unconnected-(JP16-Pad5)") (class "Default")
      (node (ref "JP16") (pin "5") (pinfunction "5_5") (pintype "passive"))
    )
    (net (code "62") (name "unconnected-(JP17-Pad1)") (class "Default")
      (node (ref "JP17") (pin "1") (pinfunction "1_1") (pintype "passive"))
    )
    (net (code "63") (name "unconnected-(JP17-Pad2)") (class "Default")
      (node (ref "JP17") (pin "2") (pinfunction "2_2") (pintype "passive"))
    )
    (net (code "64") (name "unconnected-(JP17-Pad3)") (class "Default")
      (node (ref "JP17") (pin "3") (pinfunction "3_3") (pintype "passive"))
    )
    (net (code "65") (name "unconnected-(JP17-Pad4)") (class "Default")
      (node (ref "JP17") (pin "4") (pinfunction "4_4") (pintype "passive"))
    )
    (net (code "66") (name "unconnected-(JP17-Pad5)") (class "Default")
      (node (ref "JP17") (pin "5") (pinfunction "5_5") (pintype "passive"))
    )
    (net (code "67") (name "unconnected-(JP18-Pad1)") (class "Default")
      (node (ref "JP18") (pin "1") (pinfunction "1_1") (pintype "passive"))
    )
    (net (code "68") (name "unconnected-(JP18-Pad2)") (class "Default")
      (node (ref "JP18") (pin "2") (pinfunction "2_2") (pintype "passive"))
    )
    (net (code "69") (name "unconnected-(JP18-Pad3)") (class "Default")
      (node (ref "JP18") (pin "3") (pinfunction "3_3") (pintype "passive"))
    )
    (net (code "70") (name "unconnected-(JP18-Pad4)") (class "Default")
      (node (ref "JP18") (pin "4") (pinfunction "4_4") (pintype "passive"))
    )
    (net (code "71") (name "unconnected-(JP18-Pad5)") (class "Default")
      (node (ref "JP18") (pin "5") (pinfunction "5_5") (pintype "passive"))
    )
    (net (code "72") (name "unconnected-(JP19-Pad1)") (class "Default")
      (node (ref "JP19") (pin "1") (pinfunction "1_1") (pintype "passive"))
    )
    (net (code "73") (name "unconnected-(JP19-Pad2)") (class "Default")
      (node (ref "JP19") (pin "2") (pinfunction "2_2") (pintype "passive"))
    )
    (net (code "74") (name "unconnected-(JP19-Pad3)") (class "Default")
      (node (ref "JP19") (pin "3") (pinfunction "3_3") (pintype "passive"))
    )
    (net (code "75") (name "unconnected-(JP19-Pad4)") (class "Default")
      (node (ref "JP19") (pin "4") (pinfunction "4_4") (pintype "passive"))
    )
    (net (code "76") (name "unconnected-(JP19-Pad5)") (class "Default")
      (node (ref "JP19") (pin "5") (pinfunction "5_5") (pintype "passive"))
    )
    (net (code "77") (name "unconnected-(JP20-Pad1)") (class "Default")
      (node (ref "JP20") (pin "1") (pinfunction "1_1") (pintype "passive"))
    )
    (net (code "78") (name "unconnected-(JP20-Pad2)") (class "Default")
      (node (ref "JP20") (pin "2") (pinfunction "2_2") (pintype "passive"))
    )
    (net (code "79") (name "unconnected-(JP20-Pad3)") (class "Default")
      (node (ref "JP20") (pin "3") (pinfunction "3_3") (pintype "passive"))
    )
    (net (code "80") (name "unconnected-(JP20-Pad4)") (class "Default")
      (node (ref "JP20") (pin "4") (pinfunction "4_4") (pintype "passive"))
    )
    (net (code "81") (name "unconnected-(JP20-Pad5)") (class "Default")
      (node (ref "JP20") (pin "5") (pinfunction "5_5") (pintype "passive"))
    )
    (net (code "82") (name "unconnected-(JP21-Pad1)") (class "Default")
      (node (ref "JP21") (pin "1") (pinfunction "1_1") (pintype "passive"))
    )
    (net (code "83") (name "unconnected-(JP21-Pad2)") (class "Default")
      (node (ref "JP21") (pin "2") (pinfunction "2_2") (pintype "passive"))
    )
    (net (code "84") (name "unconnected-(JP21-Pad3)") (class "Default")
      (node (ref "JP21") (pin "3") (pinfunction "3_3") (pintype "passive"))
    )
    (net (code "85") (name "unconnected-(JP21-Pad4)") (class "Default")
      (node (ref "JP21") (pin "4") (pinfunction "4_4") (pintype "passive"))
    )
    (net (code "86") (name "unconnected-(JP21-Pad5)") (class "Default")
      (node (ref "JP21") (pin "5") (pinfunction "5_5") (pintype "passive"))
    )
    (net (code "87") (name "unconnected-(JP22-Pad1)") (class "Default")
      (node (ref "JP22") (pin "1") (pinfunction "1_1") (pintype "passive"))
    )
    (net (code "88") (name "unconnected-(JP22-Pad2)") (class "Default")
      (node (ref "JP22") (pin "2") (pinfunction "2_2") (pintype "passive"))
    )
    (net (code "89") (name "unconnected-(JP22-Pad3)") (class "Default")
      (node (ref "JP22") (pin "3") (pinfunction "3_3") (pintype "passive"))
    )
    (net (code "90") (name "unconnected-(JP22-Pad4)") (class "Default")
      (node (ref "JP22") (pin "4") (pinfunction "4_4") (pintype "passive"))
    )
    (net (code "91") (name "unconnected-(JP22-Pad5)") (class "Default")
      (node (ref "JP22") (pin "5") (pinfunction "5_5") (pintype "passive"))
    )
    (net (code "92") (name "unconnected-(JP23-Pad1)") (class "Default")
      (node (ref "JP23") (pin "1") (pinfunction "1_1") (pintype "passive"))
    )
    (net (code "93") (name "unconnected-(JP23-Pad2)") (class "Default")
      (node (ref "JP23") (pin "2") (pinfunction "2_2") (pintype "passive"))
    )
    (net (code "94") (name "unconnected-(JP23-Pad3)") (class "Default")
      (node (ref "JP23") (pin "3") (pinfunction "3_3") (pintype "passive"))
    )
    (net (code "95") (name "unconnected-(JP23-Pad4)") (class "Default")
      (node (ref "JP23") (pin "4") (pinfunction "4_4") (pintype "passive"))
    )
    (net (code "96") (name "unconnected-(JP23-Pad5)") (class "Default")
      (node (ref "JP23") (pin "5") (pinfunction "5_5") (pintype "passive"))
    )
    (net (code "97") (name "unconnected-(JP25-Pad1)") (class "Default")
      (node (ref "JP25") (pin "1") (pinfunction "1_1") (pintype "passive"))
    )
    (net (code "98") (name "unconnected-(JP25-Pad2)") (class "Default")
      (node (ref "JP25") (pin "2") (pinfunction "2_2") (pintype "passive"))
    )
    (net (code "99") (name "unconnected-(JP25-Pad3)") (class "Default")
      (node (ref "JP25") (pin "3") (pinfunction "3_3") (pintype "passive"))
    )
    (net (code "100") (name "unconnected-(JP25-Pad4)") (class "Default")
      (node (ref "JP25") (pin "4") (pinfunction "4_4") (pintype "passive"))
    )
    (net (code "101") (name "unconnected-(JP25-Pad5)") (class "Default")
      (node (ref "JP25") (pin "5") (pinfunction "5_5") (pintype "passive"))
    )
    (net (code "102") (name "unconnected-(JP26-Pad1)") (class "Default")
      (node (ref "JP26") (pin "1") (pinfunction "1_1") (pintype "passive"))
    )
    (net (code "103") (name "unconnected-(JP26-Pad2)") (class "Default")
      (node (ref "JP26") (pin "2") (pinfunction "2_2") (pintype "passive"))
    )
    (net (code "104") (name "unconnected-(JP26-Pad3)") (class "Default")
      (node (ref "JP26") (pin "3") (pinfunction "3_3") (pintype "passive"))
    )
    (net (code "105") (name "unconnected-(JP26-Pad4)") (class "Default")
      (node (ref "JP26") (pin "4") (pinfunction "4_4") (pintype "passive"))
    )
    (net (code "106") (name "unconnected-(JP26-Pad5)") (class "Default")
      (node (ref "JP26") (pin "5") (pinfunction "5_5") (pintype "passive"))
    )
    (net (code "107") (name "unconnected-(JP27-Pad1)") (class "Default")
      (node (ref "JP27") (pin "1") (pinfunction "1_1") (pintype "passive"))
    )
    (net (code "108") (name "unconnected-(JP27-Pad2)") (class "Default")
      (node (ref "JP27") (pin "2") (pinfunction "2_2") (pintype "passive"))
    )
    (net (code "109") (name "unconnected-(JP27-Pad3)") (class "Default")
      (node (ref "JP27") (pin "3") (pinfunction "3_3") (pintype "passive"))
    )
    (net (code "110") (name "unconnected-(JP27-Pad4)") (class "Default")
      (node (ref "JP27") (pin "4") (pinfunction "4_4") (pintype "passive"))
    )
    (net (code "111") (name "unconnected-(JP27-Pad5)") (class "Default")
      (node (ref "JP27") (pin "5") (pinfunction "5_5") (pintype "passive"))
    )
    (net (code "112") (name "unconnected-(JP28-Pad1)") (class "Default")
      (node (ref "JP28") (pin "1") (pinfunction "1_1") (pintype "passive"))
    )
    (net (code "113") (name "unconnected-(JP28-Pad2)") (class "Default")
      (node (ref "JP28") (pin "2") (pinfunction "2_2") (pintype "passive"))
    )
    (net (code "114") (name "unconnected-(JP28-Pad3)") (class "Default")
      (node (ref "JP28") (pin "3") (pinfunction "3_3") (pintype "passive"))
    )
    (net (code "115") (name "unconnected-(JP28-Pad4)") (class "Default")
      (node (ref "JP28") (pin "4") (pinfunction "4_4") (pintype "passive"))
    )
    (net (code "116") (name "unconnected-(JP28-Pad5)") (class "Default")
      (node (ref "JP28") (pin "5") (pinfunction "5_5") (pintype "passive"))
    )
    (net (code "117") (name "unconnected-(JP29-Pad1)") (class "Default")
      (node (ref "JP29") (pin "1") (pinfunction "1_1") (pintype "passive"))
    )
    (net (code "118") (name "unconnected-(JP29-Pad2)") (class "Default")
      (node (ref "JP29") (pin "2") (pinfunction "2_2") (pintype "passive"))
    )
    (net (code "119") (name "unconnected-(JP29-Pad3)") (class "Default")
      (node (ref "JP29") (pin "3") (pinfunction "3_3") (pintype "passive"))
    )
    (net (code "120") (name "unconnected-(JP29-Pad4)") (class "Default")
      (node (ref "JP29") (pin "4") (pinfunction "4_4") (pintype "passive"))
    )
    (net (code "121") (name "unconnected-(JP29-Pad5)") (class "Default")
      (node (ref "JP29") (pin "5") (pinfunction "5_5") (pintype "passive"))
    )
    (net (code "122") (name "unconnected-(JP30-Pad1)") (class "Default")
      (node (ref "JP30") (pin "1") (pinfunction "1_1") (pintype "passive"))
    )
    (net (code "123") (name "unconnected-(JP30-Pad2)") (class "Default")
      (node (ref "JP30") (pin "2") (pinfunction "2_2") (pintype "passive"))
    )
    (net (code "124") (name "unconnected-(JP30-Pad3)") (class "Default")
      (node (ref "JP30") (pin "3") (pinfunction "3_3") (pintype "passive"))
    )
    (net (code "125") (name "unconnected-(JP30-Pad4)") (class "Default")
      (node (ref "JP30") (pin "4") (pinfunction "4_4") (pintype "passive"))
    )
    (net (code "126") (name "unconnected-(JP30-Pad5)") (class "Default")
      (node (ref "JP30") (pin "5") (pinfunction "5_5") (pintype "passive"))
    )
    (net (code "127") (name "unconnected-(JP31-Pad1)") (class "Default")
      (node (ref "JP31") (pin "1") (pinfunction "1_1") (pintype "passive"))
    )
    (net (code "128") (name "unconnected-(JP31-Pad2)") (class "Default")
      (node (ref "JP31") (pin "2") (pinfunction "2_2") (pintype "passive"))
    )
    (net (code "129") (name "unconnected-(JP31-Pad3)") (class "Default")
      (node (ref "JP31") (pin "3") (pinfunction "3_3") (pintype "passive"))
    )
    (net (code "130") (name "unconnected-(JP31-Pad4)") (class "Default")
      (node (ref "JP31") (pin "4") (pinfunction "4_4") (pintype "passive"))
    )
    (net (code "131") (name "unconnected-(JP31-Pad5)") (class "Default")
      (node (ref "JP31") (pin "5") (pinfunction "5_5") (pintype "passive"))
    )
    (net (code "132") (name "unconnected-(U$1-NC-PadNC@1)") (class "Default")
      (node (ref "U$1") (pin "NC@1") (pinfunction "NC_NC@1") (pintype "bidirectional"))
    )
    (net (code "133") (name "unconnected-(U$1-NC-PadNC@2)") (class "Default")
      (node (ref "U$1") (pin "NC@2") (pinfunction "NC_NC@2") (pintype "bidirectional"))
    )
    (net (code "134") (name "unconnected-(U$2-NC-PadNC@1)") (class "Default")
      (node (ref "U$2") (pin "NC@1") (pinfunction "NC_NC@1") (pintype "bidirectional"))
    )
    (net (code "135") (name "unconnected-(U$2-NC-PadNC@2)") (class "Default")
      (node (ref "U$2") (pin "NC@2") (pinfunction "NC_NC@2") (pintype "bidirectional"))
    )
    (net (code "136") (name "unconnected-(X2-Pad2)") (class "Default")
      (node (ref "X2") (pin "2") (pinfunction "2_2") (pintype "passive"))
    )
    (net (code "137") (name "unconnected-(X2-Pad3)") (class "Default")
      (node (ref "X2") (pin "3") (pinfunction "3_3") (pintype "passive"))
    )
  )
)
